# sensor-hub-fr-fl.net
KiCad netlist of a schematic drawn in EAGLE
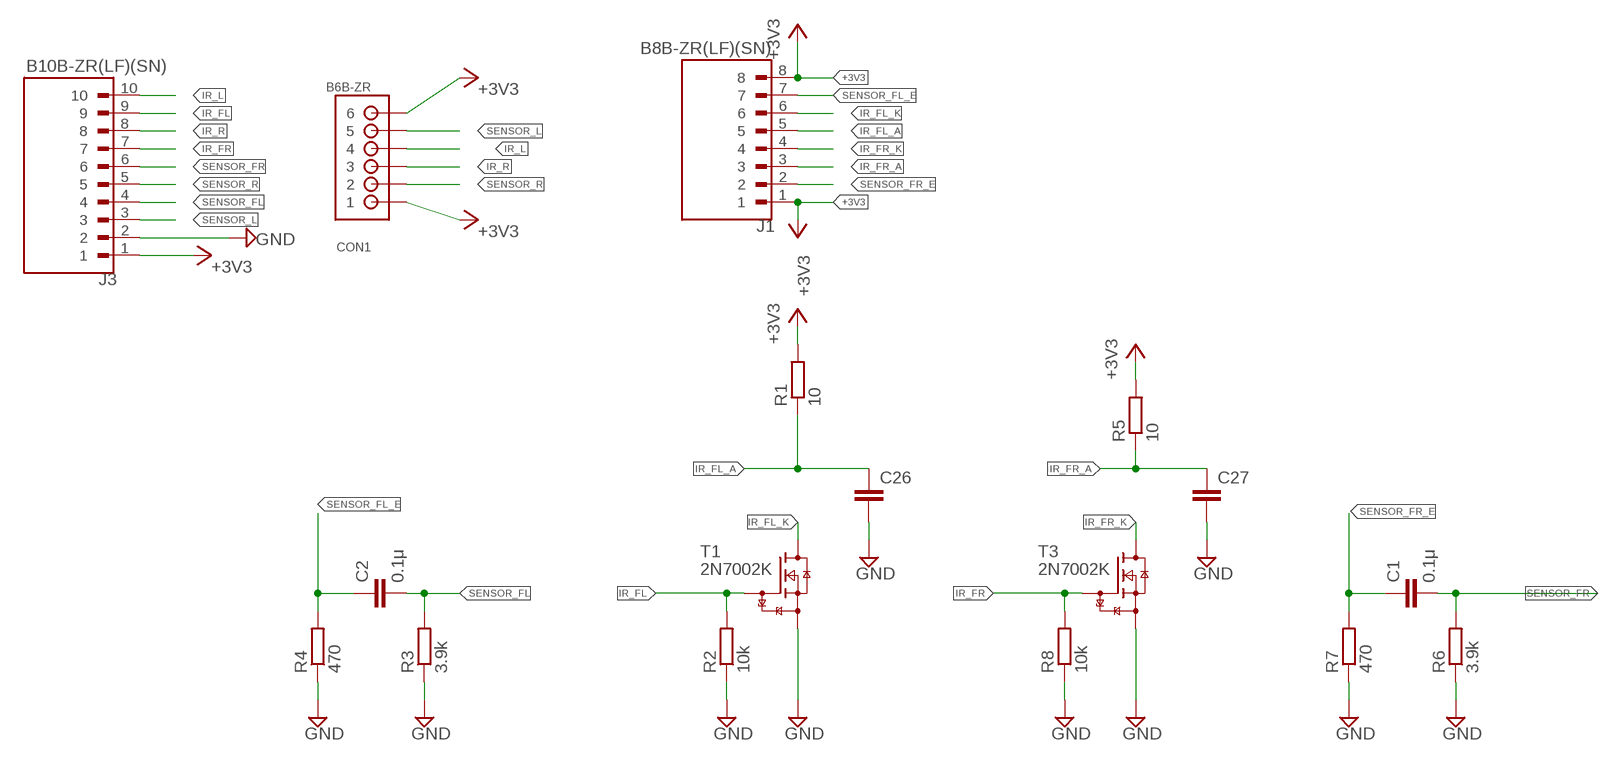
[diagram p0: schematic, sheet 1]

(export (version "E")
  (design (tool "Eeschema 10.0.6"))
  (components
    (comp (ref "C1")
      (value "0.1μ")
      (footprint "eagle-import:C0603")
      (libsource (lib "eagle-import") (part "C-EUC0603"))
    )
    (comp (ref "C2")
      (value "0.1μ")
      (footprint "eagle-import:C0603")
      (libsource (lib "eagle-import") (part "C-EUC0603"))
    )
    (comp (ref "C26")
      (value "C-EUC1206")
      (footprint "eagle-import:C1206")
      (libsource (lib "eagle-import") (part "C-EUC1206"))
    )
    (comp (ref "C27")
      (value "C-EUC1206")
      (footprint "eagle-import:C1206")
      (libsource (lib "eagle-import") (part "C-EUC1206"))
    )
    (comp (ref "CON1")
      (value "B6B-ZR")
      (footprint "eagle-import:B6B-ZR")
      (libsource (lib "eagle-import") (part "B6B-ZR"))
    )
    (comp (ref "J1")
      (value "B8B-ZR(LF)(SN)")
      (footprint "eagle-import:JST_B8B-ZR(LF)(SN)")
      (fields (field (name "MF") "JST") (field (name "MP") "B8B-ZR (LF)(SN)"))
      (libsource (lib "eagle-import") (part "B8B-ZR(LF)(SN)"))
    )
    (comp (ref "J3")
      (value "B10B-ZR(LF)(SN)")
      (footprint "eagle-import:JST_B10B-ZR(LF)(SN)")
      (fields (field (name "MF") "JST Sales America Inc."))
      (libsource (lib "eagle-import") (part "B10B-ZR(LF)(SN)"))
    )
    (comp (ref "R1")
      (value "10")
      (footprint "eagle-import:R0603")
      (libsource (lib "eagle-import") (part "R-EU_R0603"))
    )
    (comp (ref "R2")
      (value "10k")
      (footprint "eagle-import:R0603")
      (libsource (lib "eagle-import") (part "R-EU_R0603"))
    )
    (comp (ref "R3")
      (value "3.9k")
      (footprint "eagle-import:R0603")
      (libsource (lib "eagle-import") (part "R-EU_R0603"))
    )
    (comp (ref "R4")
      (value "470")
      (footprint "eagle-import:R0603")
      (libsource (lib "eagle-import") (part "R-EU_R0603"))
    )
    (comp (ref "R5")
      (value "10")
      (footprint "eagle-import:R0603")
      (libsource (lib "eagle-import") (part "R-EU_R0603"))
    )
    (comp (ref "R6")
      (value "3.9k")
      (footprint "eagle-import:R0603")
      (libsource (lib "eagle-import") (part "R-EU_R0603"))
    )
    (comp (ref "R7")
      (value "470")
      (footprint "eagle-import:R0603")
      (libsource (lib "eagle-import") (part "R-EU_R0603"))
    )
    (comp (ref "R8")
      (value "10k")
      (footprint "eagle-import:R0603")
      (libsource (lib "eagle-import") (part "R-EU_R0603"))
    )
    (comp (ref "T1")
      (value "2N7002K")
      (footprint "eagle-import:SOT23")
      (libsource (lib "eagle-import") (part "2N7002K"))
    )
    (comp (ref "T3")
      (value "2N7002K")
      (footprint "eagle-import:SOT23")
      (libsource (lib "eagle-import") (part "2N7002K"))
    )
  )
  (nets
    (net (code "1") (name "+3V3") (class "Default")
      (node (ref "CON1") (pin "1") (pinfunction "1_1") (pintype "bidirectional"))
      (node (ref "CON1") (pin "6") (pinfunction "6_6") (pintype "bidirectional"))
      (node (ref "J1") (pin "1") (pinfunction "1_1") (pintype "passive"))
      (node (ref "J1") (pin "8") (pinfunction "8_8") (pintype "passive"))
      (node (ref "J3") (pin "1") (pinfunction "1_1") (pintype "passive"))
      (node (ref "R1") (pin "2") (pinfunction "2_2") (pintype "passive"))
      (node (ref "R5") (pin "2") (pinfunction "2_2") (pintype "passive"))
    )
    (net (code "2") (name "GND") (class "Default")
      (node (ref "C26") (pin "2") (pinfunction "2_2") (pintype "passive"))
      (node (ref "C27") (pin "2") (pinfunction "2_2") (pintype "passive"))
      (node (ref "J3") (pin "2") (pinfunction "2_2") (pintype "passive"))
      (node (ref "R2") (pin "1") (pinfunction "1_1") (pintype "passive"))
      (node (ref "R3") (pin "1") (pinfunction "1_1") (pintype "passive"))
      (node (ref "R4") (pin "1") (pinfunction "1_1") (pintype "passive"))
      (node (ref "R6") (pin "1") (pinfunction "1_1") (pintype "passive"))
      (node (ref "R7") (pin "1") (pinfunction "1_1") (pintype "passive"))
      (node (ref "R8") (pin "1") (pinfunction "1_1") (pintype "passive"))
      (node (ref "T1") (pin "2") (pinfunction "S_2") (pintype "passive"))
      (node (ref "T3") (pin "2") (pinfunction "S_2") (pintype "passive"))
    )
    (net (code "3") (name "IR_FL") (class "Default")
      (node (ref "J3") (pin "9") (pinfunction "9_9") (pintype "passive"))
      (node (ref "R2") (pin "2") (pinfunction "2_2") (pintype "passive"))
      (node (ref "T1") (pin "1") (pinfunction "G_1") (pintype "passive"))
    )
    (net (code "4") (name "IR_FL_A") (class "Default")
      (node (ref "C26") (pin "1") (pinfunction "1_1") (pintype "passive"))
      (node (ref "J1") (pin "5") (pinfunction "5_5") (pintype "passive"))
      (node (ref "R1") (pin "1") (pinfunction "1_1") (pintype "passive"))
    )
    (net (code "5") (name "IR_FL_K") (class "Default")
      (node (ref "J1") (pin "6") (pinfunction "6_6") (pintype "passive"))
      (node (ref "T1") (pin "3") (pinfunction "D_3") (pintype "passive"))
    )
    (net (code "6") (name "IR_FR") (class "Default")
      (node (ref "J3") (pin "7") (pinfunction "7_7") (pintype "passive"))
      (node (ref "R8") (pin "2") (pinfunction "2_2") (pintype "passive"))
      (node (ref "T3") (pin "1") (pinfunction "G_1") (pintype "passive"))
    )
    (net (code "7") (name "IR_FR_A") (class "Default")
      (node (ref "C27") (pin "1") (pinfunction "1_1") (pintype "passive"))
      (node (ref "J1") (pin "3") (pinfunction "3_3") (pintype "passive"))
      (node (ref "R5") (pin "1") (pinfunction "1_1") (pintype "passive"))
    )
    (net (code "8") (name "IR_FR_K") (class "Default")
      (node (ref "J1") (pin "4") (pinfunction "4_4") (pintype "passive"))
      (node (ref "T3") (pin "3") (pinfunction "D_3") (pintype "passive"))
    )
    (net (code "9") (name "IR_L") (class "Default")
      (node (ref "CON1") (pin "4") (pinfunction "4_4") (pintype "bidirectional"))
      (node (ref "J3") (pin "10") (pinfunction "10_10") (pintype "passive"))
    )
    (net (code "10") (name "IR_R") (class "Default")
      (node (ref "CON1") (pin "3") (pinfunction "3_3") (pintype "bidirectional"))
      (node (ref "J3") (pin "8") (pinfunction "8_8") (pintype "passive"))
    )
    (net (code "11") (name "SENSOR_FL") (class "Default")
      (node (ref "C2") (pin "2") (pinfunction "2_2") (pintype "passive"))
      (node (ref "J3") (pin "4") (pinfunction "4_4") (pintype "passive"))
      (node (ref "R3") (pin "2") (pinfunction "2_2") (pintype "passive"))
    )
    (net (code "12") (name "SENSOR_FL_E") (class "Default")
      (node (ref "C2") (pin "1") (pinfunction "1_1") (pintype "passive"))
      (node (ref "J1") (pin "7") (pinfunction "7_7") (pintype "passive"))
      (node (ref "R4") (pin "2") (pinfunction "2_2") (pintype "passive"))
    )
    (net (code "13") (name "SENSOR_FR") (class "Default")
      (node (ref "C1") (pin "2") (pinfunction "2_2") (pintype "passive"))
      (node (ref "J3") (pin "6") (pinfunction "6_6") (pintype "passive"))
      (node (ref "R6") (pin "2") (pinfunction "2_2") (pintype "passive"))
    )
    (net (code "14") (name "SENSOR_FR_E") (class "Default")
      (node (ref "C1") (pin "1") (pinfunction "1_1") (pintype "passive"))
      (node (ref "J1") (pin "2") (pinfunction "2_2") (pintype "passive"))
      (node (ref "R7") (pin "2") (pinfunction "2_2") (pintype "passive"))
    )
    (net (code "15") (name "SENSOR_L") (class "Default")
      (node (ref "CON1") (pin "5") (pinfunction "5_5") (pintype "bidirectional"))
      (node (ref "J3") (pin "3") (pinfunction "3_3") (pintype "passive"))
    )
    (net (code "16") (name "SENSOR_R") (class "Default")
      (node (ref "CON1") (pin "2") (pinfunction "2_2") (pintype "bidirectional"))
      (node (ref "J3") (pin "5") (pinfunction "5_5") (pintype "passive"))
    )
  )
)
